# puck_pcb.net
KiCad netlist of a schematic drawn in EAGLE
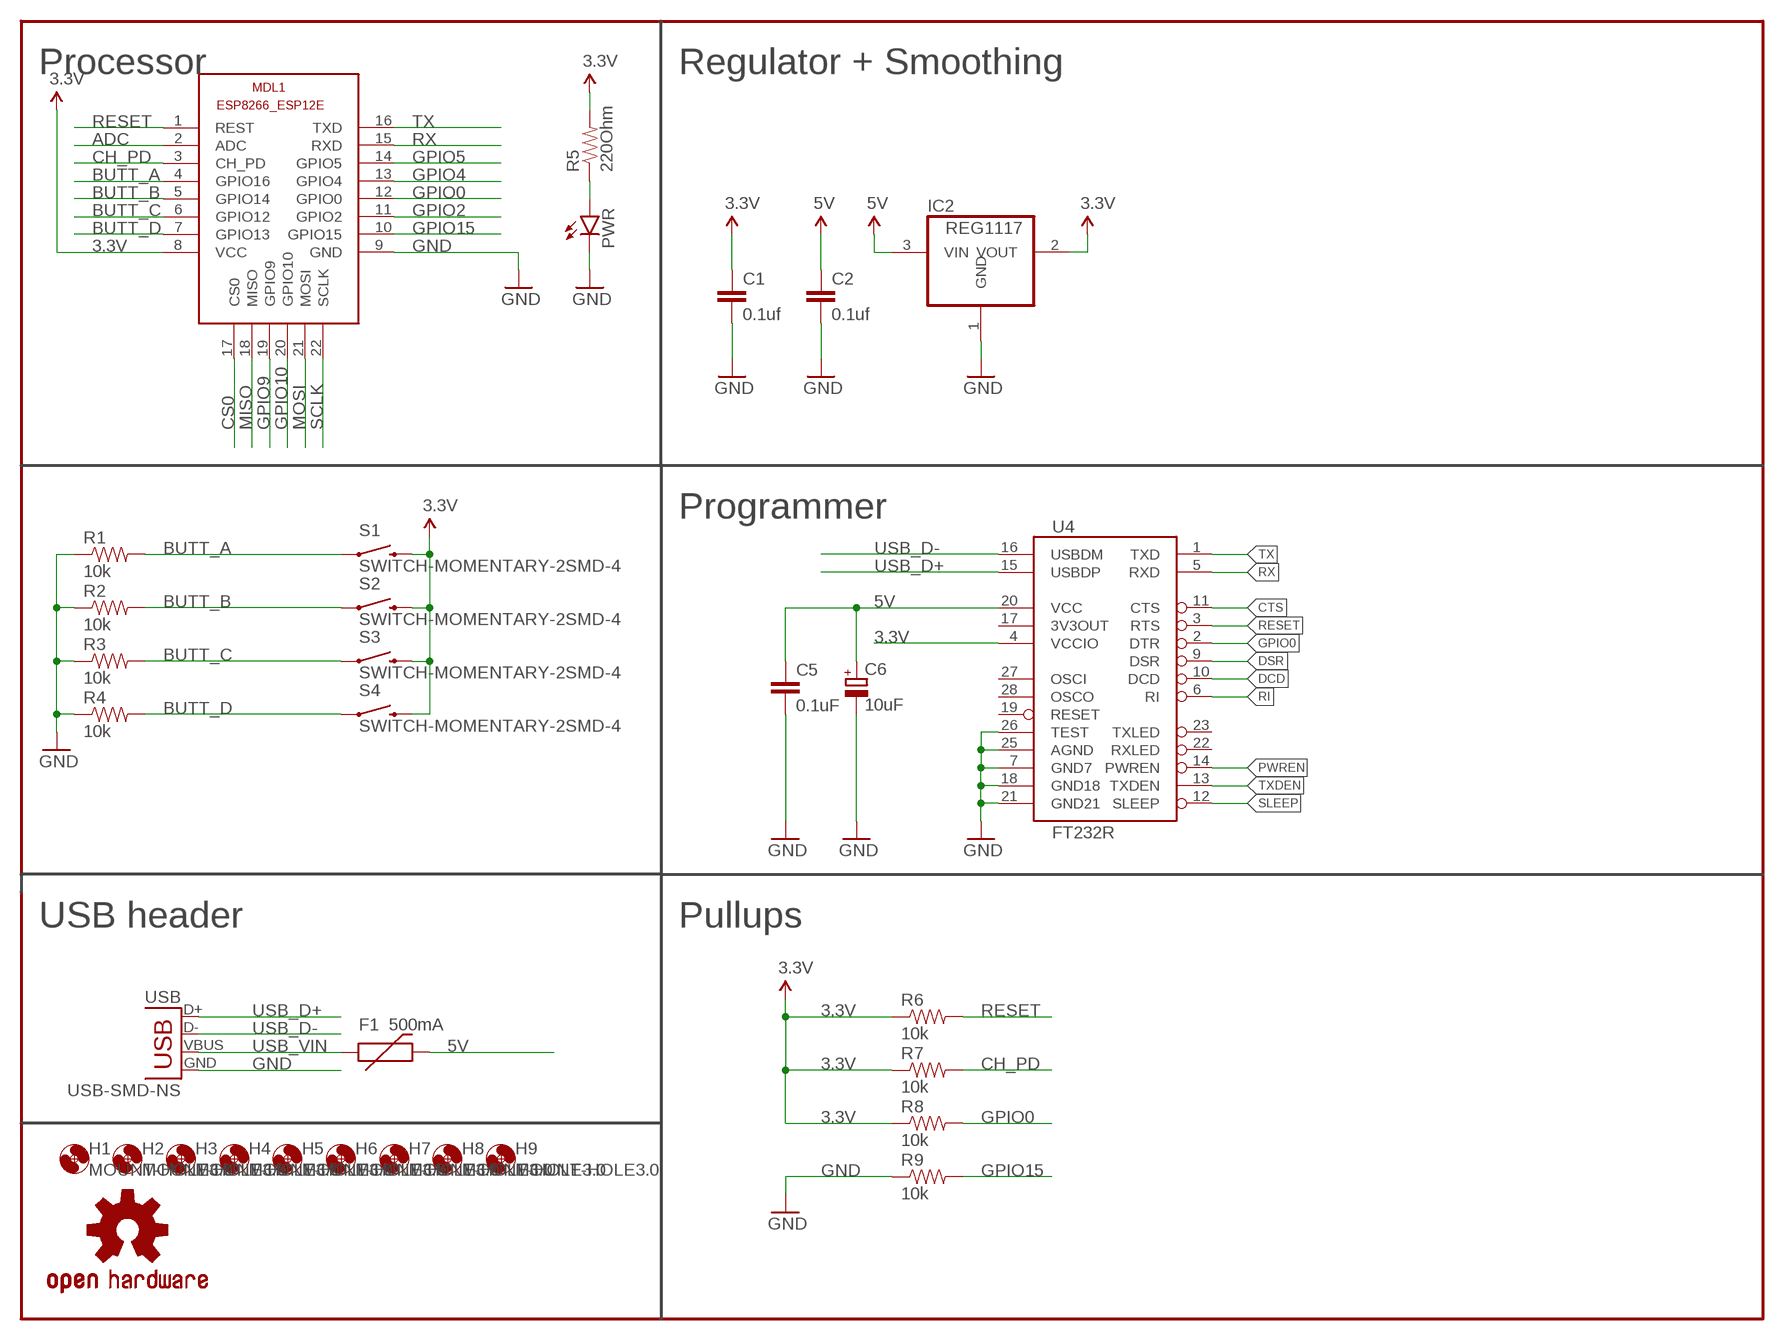
[diagram p0: schematic, sheet 1]

(export (version "E")
  (design (tool "Eeschema 10.0.6"))
  (components
    (comp (ref "C1")
      (value "0.1uf")
      (footprint "eagle-import:1206")
      (libsource (lib "eagle-import") (part "CAP1206"))
    )
    (comp (ref "C2")
      (value "0.1uf")
      (footprint "eagle-import:1206")
      (libsource (lib "eagle-import") (part "CAP1206"))
    )
    (comp (ref "C5")
      (value "0.1uF")
      (footprint "eagle-import:C1206K")
      (libsource (lib "eagle-import") (part "C-EUC1206K"))
    )
    (comp (ref "C6")
      (value "10uF")
      (footprint "eagle-import:SMC_A")
      (libsource (lib "eagle-import") (part "CPOL-EUSMCA"))
    )
    (comp (ref "F1")
      (value "500mA")
      (footprint "eagle-import:PTC-1206")
      (libsource (lib "eagle-import") (part "PTCSMD"))
    )
    (comp (ref "FRAME2")
      (value "FRAME-LETTERNO_PACKAGE")
      (footprint "eagle-import:DUMMY")
      (fields (field (name "DESIGNER") "Nobody"))
      (libsource (lib "eagle-import") (part "FRAME-LETTERNO_PACKAGE"))
    )
    (comp (ref "H1")
      (value "MOUNT-HOLE3.0")
      (footprint "eagle-import:3,0")
      (libsource (lib "eagle-import") (part "MOUNT-HOLE3.0"))
    )
    (comp (ref "H2")
      (value "MOUNT-HOLE3.0")
      (footprint "eagle-import:3,0")
      (libsource (lib "eagle-import") (part "MOUNT-HOLE3.0"))
    )
    (comp (ref "H3")
      (value "MOUNT-HOLE3.0")
      (footprint "eagle-import:3,0")
      (libsource (lib "eagle-import") (part "MOUNT-HOLE3.0"))
    )
    (comp (ref "H4")
      (value "MOUNT-HOLE3.0")
      (footprint "eagle-import:3,0")
      (libsource (lib "eagle-import") (part "MOUNT-HOLE3.0"))
    )
    (comp (ref "H5")
      (value "MOUNT-HOLE3.0")
      (footprint "eagle-import:3,0")
      (libsource (lib "eagle-import") (part "MOUNT-HOLE3.0"))
    )
    (comp (ref "H6")
      (value "MOUNT-HOLE3.0")
      (footprint "eagle-import:3,0")
      (libsource (lib "eagle-import") (part "MOUNT-HOLE3.0"))
    )
    (comp (ref "H7")
      (value "MOUNT-HOLE3.0")
      (footprint "eagle-import:3,0")
      (libsource (lib "eagle-import") (part "MOUNT-HOLE3.0"))
    )
    (comp (ref "H8")
      (value "MOUNT-HOLE3.0")
      (footprint "eagle-import:3,0")
      (libsource (lib "eagle-import") (part "MOUNT-HOLE3.0"))
    )
    (comp (ref "H9")
      (value "MOUNT-HOLE3.0")
      (footprint "eagle-import:3,0")
      (libsource (lib "eagle-import") (part "MOUNT-HOLE3.0"))
    )
    (comp (ref "IC2")
      (value "REG1117")
      (footprint "eagle-import:SOT223")
      (libsource (lib "eagle-import") (part "REG1117"))
    )
    (comp (ref "LOGO1")
      (value "OSHW-LOGOS")
      (footprint "eagle-import:OSHW-LOGO-S")
      (libsource (lib "eagle-import") (part "OSHW-LOGOS"))
    )
    (comp (ref "MDL1")
      (value "ESP8266-12EESP8266-ESP12E")
      (footprint "eagle-import:ESP8266-ESP12E")
      (libsource (lib "eagle-import") (part "ESP8266-12EESP8266-ESP12E"))
    )
    (comp (ref "PWR")
      (value "LED1206")
      (footprint "eagle-import:LED-1206")
      (libsource (lib "eagle-import") (part "LED1206"))
    )
    (comp (ref "R1")
      (value "10k")
      (footprint "eagle-import:1206")
      (libsource (lib "eagle-import") (part "RESISTOR1206"))
    )
    (comp (ref "R2")
      (value "10k")
      (footprint "eagle-import:1206")
      (libsource (lib "eagle-import") (part "RESISTOR1206"))
    )
    (comp (ref "R3")
      (value "10k")
      (footprint "eagle-import:1206")
      (libsource (lib "eagle-import") (part "RESISTOR1206"))
    )
    (comp (ref "R4")
      (value "10k")
      (footprint "eagle-import:1206")
      (libsource (lib "eagle-import") (part "RESISTOR1206"))
    )
    (comp (ref "R5")
      (value "220Ohm")
      (footprint "eagle-import:1206")
      (libsource (lib "eagle-import") (part "RESISTOR1206"))
    )
    (comp (ref "R6")
      (value "10k")
      (footprint "eagle-import:1206")
      (libsource (lib "eagle-import") (part "RESISTOR1206"))
    )
    (comp (ref "R7")
      (value "10k")
      (footprint "eagle-import:1206")
      (libsource (lib "eagle-import") (part "RESISTOR1206"))
    )
    (comp (ref "R8")
      (value "10k")
      (footprint "eagle-import:1206")
      (libsource (lib "eagle-import") (part "RESISTOR1206"))
    )
    (comp (ref "R9")
      (value "10k")
      (footprint "eagle-import:1206")
      (libsource (lib "eagle-import") (part "RESISTOR1206"))
    )
    (comp (ref "S1")
      (value "SWITCH-MOMENTARY-2SMD-4")
      (footprint "eagle-import:TACTILE_SWITCH_TALL")
      (libsource (lib "eagle-import") (part "SWITCH-MOMENTARY-2SMD-4"))
    )
    (comp (ref "S2")
      (value "SWITCH-MOMENTARY-2SMD-4")
      (footprint "eagle-import:TACTILE_SWITCH_TALL")
      (libsource (lib "eagle-import") (part "SWITCH-MOMENTARY-2SMD-4"))
    )
    (comp (ref "S3")
      (value "SWITCH-MOMENTARY-2SMD-4")
      (footprint "eagle-import:TACTILE_SWITCH_TALL")
      (libsource (lib "eagle-import") (part "SWITCH-MOMENTARY-2SMD-4"))
    )
    (comp (ref "S4")
      (value "SWITCH-MOMENTARY-2SMD-4")
      (footprint "eagle-import:TACTILE_SWITCH_TALL")
      (libsource (lib "eagle-import") (part "SWITCH-MOMENTARY-2SMD-4"))
    )
    (comp (ref "U4")
      (value "FT232R")
      (footprint "eagle-import:SSOP28DB")
      (libsource (lib "eagle-import") (part "FT232RLSSOP"))
    )
    (comp (ref "USB")
      (value "USB-SMD-NS")
      (footprint "eagle-import:USB-MINIB-NOSTOP")
      (libsource (lib "eagle-import") (part "USB-SMD-NS"))
    )
  )
  (nets
    (net (code "1") (name "/ADC") (class "Default")
      (node (ref "MDL1") (pin "2") (pinfunction "ADC_2") (pintype "bidirectional"))
    )
    (net (code "2") (name "/BUTT_A") (class "Default")
      (node (ref "MDL1") (pin "4") (pinfunction "GPIO16_4") (pintype "bidirectional"))
      (node (ref "R1") (pin "2") (pinfunction "2_2") (pintype "passive"))
      (node (ref "S1") (pin "A2") (pinfunction "1_A2") (pintype "passive"))
    )
    (net (code "3") (name "/BUTT_B") (class "Default")
      (node (ref "MDL1") (pin "5") (pinfunction "GPIO14_5") (pintype "bidirectional"))
      (node (ref "R2") (pin "2") (pinfunction "2_2") (pintype "passive"))
      (node (ref "S2") (pin "A2") (pinfunction "1_A2") (pintype "passive"))
    )
    (net (code "4") (name "/BUTT_C") (class "Default")
      (node (ref "MDL1") (pin "6") (pinfunction "GPIO12_6") (pintype "bidirectional"))
      (node (ref "R3") (pin "2") (pinfunction "2_2") (pintype "passive"))
      (node (ref "S3") (pin "A2") (pinfunction "1_A2") (pintype "passive"))
    )
    (net (code "5") (name "/BUTT_D") (class "Default")
      (node (ref "MDL1") (pin "7") (pinfunction "GPIO13_7") (pintype "bidirectional"))
      (node (ref "R4") (pin "2") (pinfunction "2_2") (pintype "passive"))
      (node (ref "S4") (pin "A2") (pinfunction "1_A2") (pintype "passive"))
    )
    (net (code "6") (name "/CH_PD") (class "Default")
      (node (ref "MDL1") (pin "3") (pinfunction "CH_PD_3") (pintype "bidirectional"))
      (node (ref "R7") (pin "2") (pinfunction "2_2") (pintype "passive"))
    )
    (net (code "7") (name "/CS0") (class "Default")
      (node (ref "MDL1") (pin "17") (pinfunction "CS0_17") (pintype "bidirectional"))
    )
    (net (code "8") (name "/GPIO2") (class "Default")
      (node (ref "MDL1") (pin "11") (pinfunction "GPIO2_11") (pintype "bidirectional"))
    )
    (net (code "9") (name "/GPIO4") (class "Default")
      (node (ref "MDL1") (pin "13") (pinfunction "GPIO4_13") (pintype "bidirectional"))
    )
    (net (code "10") (name "/GPIO5") (class "Default")
      (node (ref "MDL1") (pin "14") (pinfunction "GPIO5_14") (pintype "bidirectional"))
    )
    (net (code "11") (name "/GPIO9") (class "Default")
      (node (ref "MDL1") (pin "19") (pinfunction "GPIO9_19") (pintype "bidirectional"))
    )
    (net (code "12") (name "/GPIO10") (class "Default")
      (node (ref "MDL1") (pin "20") (pinfunction "GPIO10_20") (pintype "bidirectional"))
    )
    (net (code "13") (name "/GPIO15") (class "Default")
      (node (ref "MDL1") (pin "10") (pinfunction "GPIO15_10") (pintype "bidirectional"))
      (node (ref "R9") (pin "2") (pinfunction "2_2") (pintype "passive"))
    )
    (net (code "14") (name "/MISO") (class "Default")
      (node (ref "MDL1") (pin "18") (pinfunction "MISO_18") (pintype "bidirectional"))
    )
    (net (code "15") (name "/MOSI") (class "Default")
      (node (ref "MDL1") (pin "21") (pinfunction "MOSI_21") (pintype "bidirectional"))
    )
    (net (code "16") (name "/SCLK") (class "Default")
      (node (ref "MDL1") (pin "22") (pinfunction "SCLK_22") (pintype "bidirectional"))
    )
    (net (code "17") (name "/USB_D+") (class "Default")
      (node (ref "U4") (pin "15") (pinfunction "USBDP_15") (pintype "bidirectional"))
      (node (ref "USB") (pin "D+") (pinfunction "D+_D+") (pintype "bidirectional"))
    )
    (net (code "18") (name "/USB_D-") (class "Default")
      (node (ref "U4") (pin "16") (pinfunction "USBDM_16") (pintype "bidirectional"))
      (node (ref "USB") (pin "D-") (pinfunction "D-_D-") (pintype "bidirectional"))
    )
    (net (code "19") (name "/USB_VIN") (class "Default")
      (node (ref "F1") (pin "1") (pinfunction "1_1") (pintype "bidirectional"))
      (node (ref "USB") (pin "VBUS") (pinfunction "VBUS_VBUS") (pintype "bidirectional"))
    )
    (net (code "20") (name "3.3V") (class "Default")
      (node (ref "C1") (pin "1") (pinfunction "1_1") (pintype "passive"))
      (node (ref "IC2") (pin "2") (pinfunction "VOUT_2") (pintype "output"))
      (node (ref "MDL1") (pin "8") (pinfunction "VCC_8") (pintype "bidirectional"))
      (node (ref "R5") (pin "2") (pinfunction "2_2") (pintype "passive"))
      (node (ref "R6") (pin "1") (pinfunction "1_1") (pintype "passive"))
      (node (ref "R7") (pin "1") (pinfunction "1_1") (pintype "passive"))
      (node (ref "R8") (pin "1") (pinfunction "1_1") (pintype "passive"))
      (node (ref "S1") (pin "B2") (pinfunction "2_B2") (pintype "passive"))
      (node (ref "S2") (pin "B2") (pinfunction "2_B2") (pintype "passive"))
      (node (ref "S3") (pin "B2") (pinfunction "2_B2") (pintype "passive"))
      (node (ref "S4") (pin "B2") (pinfunction "2_B2") (pintype "passive"))
      (node (ref "U4") (pin "4") (pinfunction "VCCIO_4") (pintype "power_in"))
    )
    (net (code "21") (name "5V") (class "Default")
      (node (ref "C2") (pin "1") (pinfunction "1_1") (pintype "passive"))
      (node (ref "C5") (pin "1") (pinfunction "1_1") (pintype "passive"))
      (node (ref "C6") (pin "+") (pinfunction "+_+") (pintype "passive"))
      (node (ref "F1") (pin "2") (pinfunction "2_2") (pintype "bidirectional"))
      (node (ref "IC2") (pin "3") (pinfunction "VIN_3") (pintype "input"))
      (node (ref "U4") (pin "20") (pinfunction "VCC_20") (pintype "power_in"))
    )
    (net (code "22") (name "CTS") (class "Default")
      (node (ref "U4") (pin "11") (pinfunction "CTS_11") (pintype "input"))
    )
    (net (code "23") (name "DCD") (class "Default")
      (node (ref "U4") (pin "10") (pinfunction "DCD_10") (pintype "input"))
    )
    (net (code "24") (name "DSR") (class "Default")
      (node (ref "U4") (pin "9") (pinfunction "DSR_9") (pintype "input"))
    )
    (net (code "25") (name "GND") (class "Default")
      (node (ref "C1") (pin "2") (pinfunction "2_2") (pintype "passive"))
      (node (ref "C2") (pin "2") (pinfunction "2_2") (pintype "passive"))
      (node (ref "C5") (pin "2") (pinfunction "2_2") (pintype "passive"))
      (node (ref "C6") (pin "-") (pinfunction "-_-") (pintype "passive"))
      (node (ref "IC2") (pin "1") (pinfunction "GND_1") (pintype "power_in"))
      (node (ref "MDL1") (pin "9") (pinfunction "GND_9") (pintype "bidirectional"))
      (node (ref "PWR") (pin "C") (pinfunction "C_C") (pintype "passive"))
      (node (ref "R1") (pin "1") (pinfunction "1_1") (pintype "passive"))
      (node (ref "R2") (pin "1") (pinfunction "1_1") (pintype "passive"))
      (node (ref "R3") (pin "1") (pinfunction "1_1") (pintype "passive"))
      (node (ref "R4") (pin "1") (pinfunction "1_1") (pintype "passive"))
      (node (ref "R9") (pin "1") (pinfunction "1_1") (pintype "passive"))
      (node (ref "U4") (pin "18") (pinfunction "GND18_18") (pintype "power_in"))
      (node (ref "U4") (pin "21") (pinfunction "GND21_21") (pintype "power_in"))
      (node (ref "U4") (pin "25") (pinfunction "AGND_25") (pintype "power_in"))
      (node (ref "U4") (pin "26") (pinfunction "TEST_26") (pintype "input"))
      (node (ref "U4") (pin "7") (pinfunction "GND7_7") (pintype "power_in"))
      (node (ref "USB") (pin "GND") (pinfunction "GND_GND") (pintype "bidirectional"))
    )
    (net (code "26") (name "GPIO0") (class "Default")
      (node (ref "MDL1") (pin "12") (pinfunction "GPIO0_12") (pintype "bidirectional"))
      (node (ref "R8") (pin "2") (pinfunction "2_2") (pintype "passive"))
      (node (ref "U4") (pin "2") (pinfunction "DTR_2") (pintype "output"))
    )
    (net (code "27") (name "Net-(PWR-PadA)") (class "Default")
      (node (ref "PWR") (pin "A") (pinfunction "A_A") (pintype "passive"))
      (node (ref "R5") (pin "1") (pinfunction "1_1") (pintype "passive"))
    )
    (net (code "28") (name "PWREN") (class "Default")
      (node (ref "U4") (pin "14") (pinfunction "PWREN_14") (pintype "input"))
    )
    (net (code "29") (name "RESET") (class "Default")
      (node (ref "MDL1") (pin "1") (pinfunction "REST_1") (pintype "bidirectional"))
      (node (ref "R6") (pin "2") (pinfunction "2_2") (pintype "passive"))
      (node (ref "U4") (pin "3") (pinfunction "RTS_3") (pintype "output"))
    )
    (net (code "30") (name "RI") (class "Default")
      (node (ref "U4") (pin "6") (pinfunction "RI_6") (pintype "input"))
    )
    (net (code "31") (name "RX") (class "Default")
      (node (ref "MDL1") (pin "15") (pinfunction "RXD_15") (pintype "bidirectional"))
      (node (ref "U4") (pin "5") (pinfunction "RXD_5") (pintype "input"))
    )
    (net (code "32") (name "SLEEP") (class "Default")
      (node (ref "U4") (pin "12") (pinfunction "SLEEP_12") (pintype "input"))
    )
    (net (code "33") (name "TX") (class "Default")
      (node (ref "MDL1") (pin "16") (pinfunction "TXD_16") (pintype "bidirectional"))
      (node (ref "U4") (pin "1") (pinfunction "TXD_1") (pintype "output"))
    )
    (net (code "34") (name "TXDEN") (class "Default")
      (node (ref "U4") (pin "13") (pinfunction "TXDEN_13") (pintype "input"))
    )
    (net (code "35") (name "unconnected-(U4-3V3OUT-Pad17)") (class "Default")
      (node (ref "U4") (pin "17") (pinfunction "3V3OUT_17") (pintype "output"))
    )
    (net (code "36") (name "unconnected-(U4-OSCI-Pad27)") (class "Default")
      (node (ref "U4") (pin "27") (pinfunction "OSCI_27") (pintype "input"))
    )
    (net (code "37") (name "unconnected-(U4-OSCO-Pad28)") (class "Default")
      (node (ref "U4") (pin "28") (pinfunction "OSCO_28") (pintype "output"))
    )
    (net (code "38") (name "unconnected-(U4-RESET-Pad19)") (class "Default")
      (node (ref "U4") (pin "19") (pinfunction "RESET_19") (pintype "input"))
    )
    (net (code "39") (name "unconnected-(U4-RXLED-Pad22)") (class "Default")
      (node (ref "U4") (pin "22") (pinfunction "RXLED_22") (pintype "input"))
    )
    (net (code "40") (name "unconnected-(U4-TXLED-Pad23)") (class "Default")
      (node (ref "U4") (pin "23") (pinfunction "TXLED_23") (pintype "input"))
    )
  )
)
